# stripboard.net
KiCad netlist of a schematic drawn in EAGLE
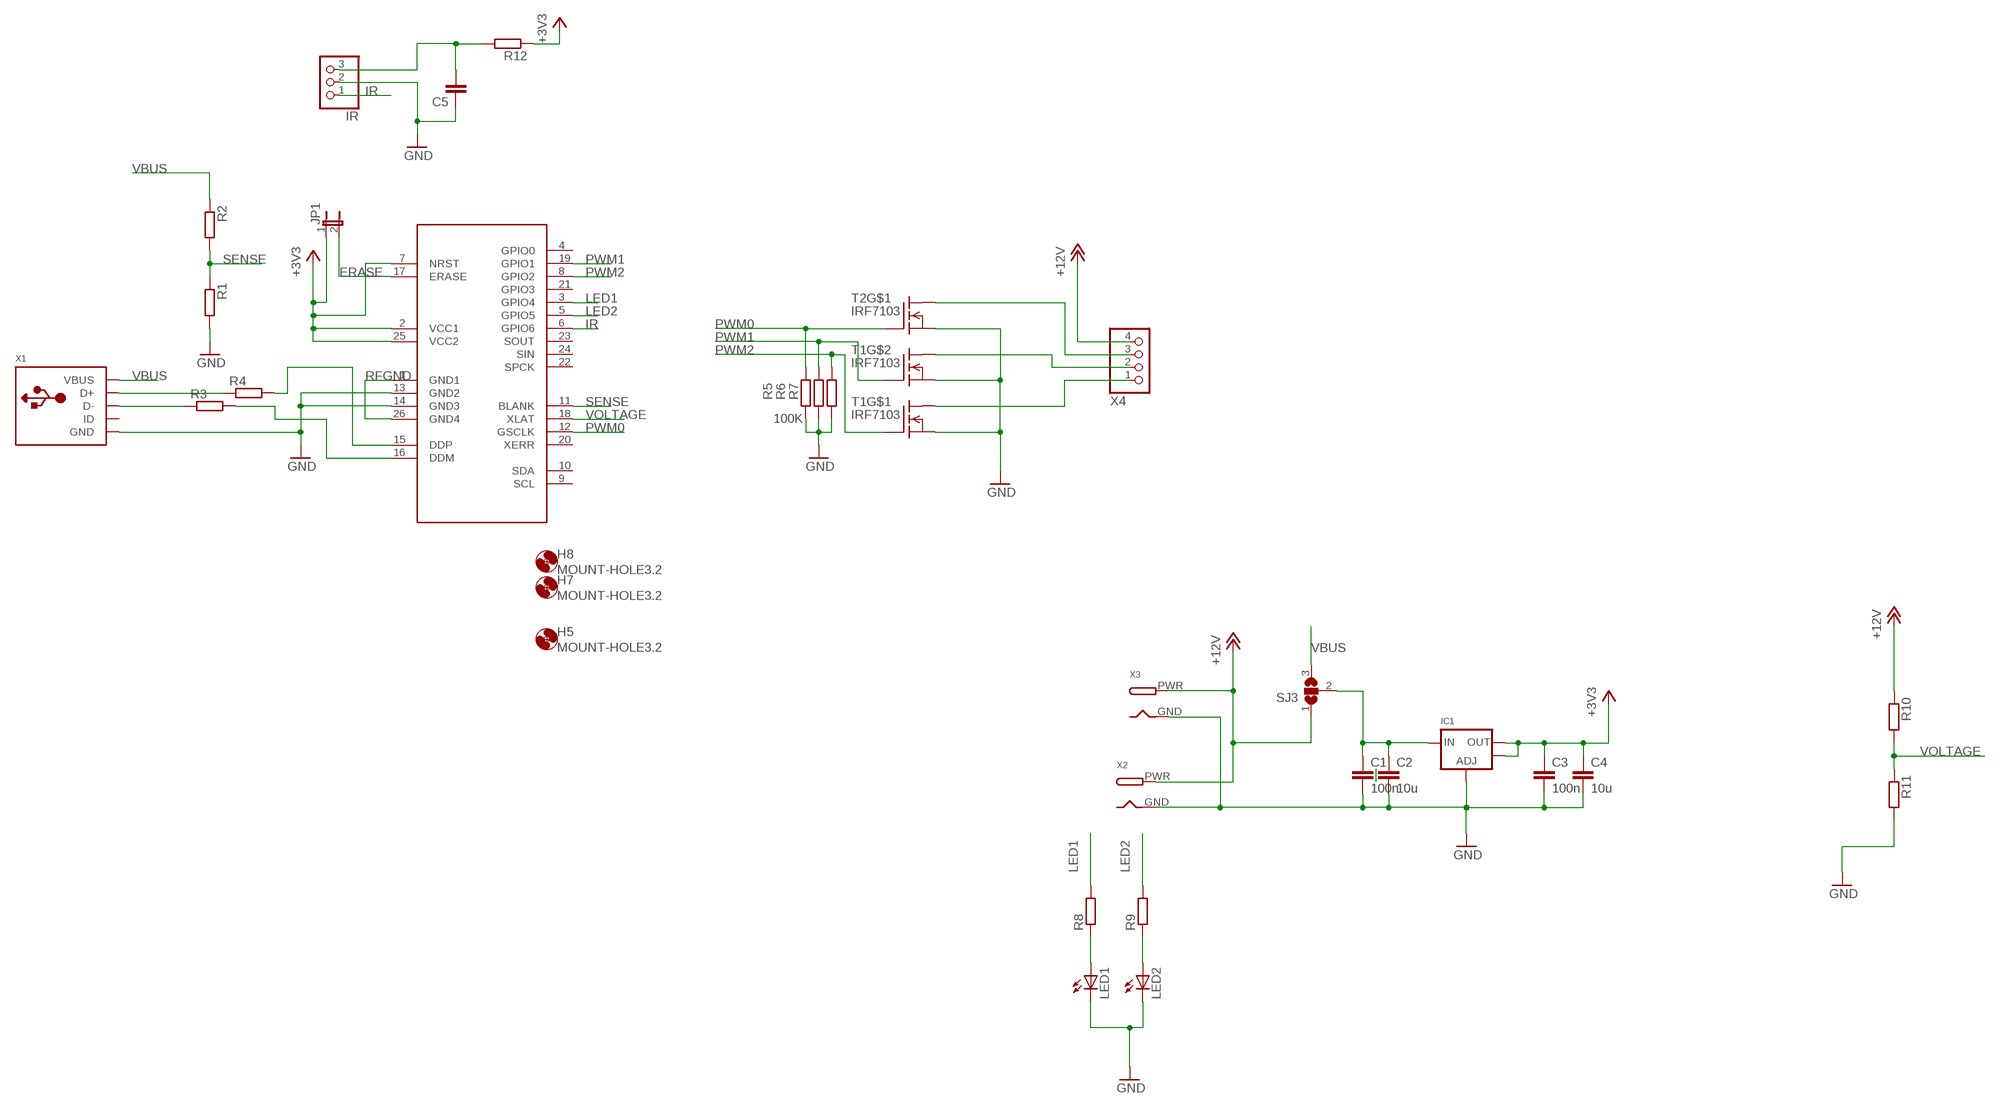
[diagram p0: schematic, sheet 1]

(export (version "E")
  (design (tool "Eeschema 10.0.6"))
  (components
    (comp (ref "C1")
      (value "100n")
      (footprint "eagle-import:C0805")
      (libsource (lib "eagle-import") (part "C-EUC0805"))
    )
    (comp (ref "C2")
      (value "10u")
      (footprint "eagle-import:C0805")
      (libsource (lib "eagle-import") (part "C-EUC0805"))
    )
    (comp (ref "C3")
      (value "100n")
      (footprint "eagle-import:C0805")
      (libsource (lib "eagle-import") (part "C-EUC0805"))
    )
    (comp (ref "C4")
      (value "10u")
      (footprint "eagle-import:C0805")
      (libsource (lib "eagle-import") (part "C-EUC0805"))
    )
    (comp (ref "C5")
      (value "C-EUC0805")
      (footprint "eagle-import:C0805")
      (libsource (lib "eagle-import") (part "C-EUC0805"))
    )
    (comp (ref "H5")
      (value "MOUNT-HOLE3.2")
      (footprint "eagle-import:3,2")
      (libsource (lib "eagle-import") (part "MOUNT-HOLE3.2"))
    )
    (comp (ref "H7")
      (value "MOUNT-HOLE3.2")
      (footprint "eagle-import:3,2")
      (libsource (lib "eagle-import") (part "MOUNT-HOLE3.2"))
    )
    (comp (ref "H8")
      (value "MOUNT-HOLE3.2")
      (footprint "eagle-import:3,2")
      (libsource (lib "eagle-import") (part "MOUNT-HOLE3.2"))
    )
    (comp (ref "IC1")
      (value "LM1117SOT223-REFLOW")
      (footprint "eagle-import:SOT223-R")
      (libsource (lib "eagle-import") (part "LM1117SOT223-REFLOW"))
    )
    (comp (ref "IR")
      (value "PINHD-1X3")
      (footprint "eagle-import:1X03")
      (libsource (lib "eagle-import") (part "PINHD-1X3"))
    )
    (comp (ref "JP1")
      (value "JP1E")
      (footprint "eagle-import:JP1")
      (libsource (lib "eagle-import") (part "JP1E"))
    )
    (comp (ref "LED1")
      (value "LEDCHIP-LED0805")
      (footprint "eagle-import:CHIP-LED0805")
      (libsource (lib "eagle-import") (part "LEDCHIP-LED0805"))
    )
    (comp (ref "LED2")
      (value "LEDCHIP-LED0805")
      (footprint "eagle-import:CHIP-LED0805")
      (libsource (lib "eagle-import") (part "LEDCHIP-LED0805"))
    )
    (comp (ref "R1")
      (value "R-EU_R0805")
      (footprint "eagle-import:R0805")
      (libsource (lib "eagle-import") (part "R-EU_R0805"))
    )
    (comp (ref "R2")
      (value "R-EU_R0805")
      (footprint "eagle-import:R0805")
      (libsource (lib "eagle-import") (part "R-EU_R0805"))
    )
    (comp (ref "R3")
      (value "R-EU_R0805")
      (footprint "eagle-import:R0805")
      (libsource (lib "eagle-import") (part "R-EU_R0805"))
    )
    (comp (ref "R4")
      (value "R-EU_R0805")
      (footprint "eagle-import:R0805")
      (libsource (lib "eagle-import") (part "R-EU_R0805"))
    )
    (comp (ref "R5")
      (value "100K")
      (footprint "eagle-import:M0805")
      (libsource (lib "eagle-import") (part "R-EU_M0805"))
    )
    (comp (ref "R6")
      (value "100K")
      (footprint "eagle-import:M0805")
      (libsource (lib "eagle-import") (part "R-EU_M0805"))
    )
    (comp (ref "R7")
      (value "100K")
      (footprint "eagle-import:M0805")
      (libsource (lib "eagle-import") (part "R-EU_M0805"))
    )
    (comp (ref "R8")
      (value "R-EU_R0805")
      (footprint "eagle-import:R0805")
      (libsource (lib "eagle-import") (part "R-EU_R0805"))
    )
    (comp (ref "R9")
      (value "R-EU_R0805")
      (footprint "eagle-import:R0805")
      (libsource (lib "eagle-import") (part "R-EU_R0805"))
    )
    (comp (ref "R10")
      (value "R-EU_R0805")
      (footprint "eagle-import:R0805")
      (libsource (lib "eagle-import") (part "R-EU_R0805"))
    )
    (comp (ref "R11")
      (value "R-EU_R0805")
      (footprint "eagle-import:R0805")
      (libsource (lib "eagle-import") (part "R-EU_R0805"))
    )
    (comp (ref "R12")
      (value "R-EU_R0805")
      (footprint "eagle-import:R0805")
      (libsource (lib "eagle-import") (part "R-EU_R0805"))
    )
    (comp (ref "SJ3")
      (value "SJ2W")
      (footprint "eagle-import:SJ_2")
      (libsource (lib "eagle-import") (part "SJ2W"))
    )
    (comp (ref "T1")
      (value "IRF7103")
      (footprint "eagle-import:SO-8")
      (libsource (lib "eagle-import") (part "IRF7103"))
    )
    (comp (ref "T2")
      (value "IRF7103")
      (footprint "eagle-import:SO-8")
      (libsource (lib "eagle-import") (part "IRF7103"))
    )
    (comp (ref "U$1")
      (value "RFBOARD")
      (footprint "eagle-import:RFBOARD")
      (libsource (lib "eagle-import") (part "RFBOARD"))
    )
    (comp (ref "X1")
      (value "USBMINIB")
      (footprint "eagle-import:USB-MINIB")
      (libsource (lib "eagle-import") (part "USBMINIB"))
    )
    (comp (ref "X2")
      (value "DCBARRELPTH")
      (footprint "eagle-import:DCJACK_2MM_PTH")
      (libsource (lib "eagle-import") (part "DCBARRELPTH"))
    )
    (comp (ref "X3")
      (value "DCBARRELPTH")
      (footprint "eagle-import:DCJACK_2MM_PTH")
      (libsource (lib "eagle-import") (part "DCBARRELPTH"))
    )
    (comp (ref "X4")
      (value "PINHD-1X4/90")
      (footprint "eagle-import:1X04_90")
      (libsource (lib "eagle-import") (part "PINHD-1X4/90"))
    )
  )
  (nets
    (net (code "1") (name "+3V3") (class "Default")
      (node (ref "C3") (pin "1") (pinfunction "1_1") (pintype "passive"))
      (node (ref "C4") (pin "1") (pinfunction "1_1") (pintype "passive"))
      (node (ref "IC1") (pin "2") (pinfunction "OUT_2") (pintype "passive"))
      (node (ref "IC1") (pin "4") (pinfunction "OUT1_4") (pintype "passive"))
      (node (ref "JP1") (pin "1") (pinfunction "1_1") (pintype "passive"))
      (node (ref "R12") (pin "1") (pinfunction "1_1") (pintype "passive"))
      (node (ref "U$1") (pin "2") (pinfunction "VCC1_2") (pintype "bidirectional"))
      (node (ref "U$1") (pin "25") (pinfunction "VCC2_25") (pintype "bidirectional"))
      (node (ref "U$1") (pin "7") (pinfunction "NRST_7") (pintype "bidirectional"))
    )
    (net (code "2") (name "+12V") (class "Default")
      (node (ref "R10") (pin "1") (pinfunction "1_1") (pintype "passive"))
      (node (ref "SJ3") (pin "1") (pinfunction "1_1") (pintype "passive"))
      (node (ref "X2") (pin "PWR") (pinfunction "PWR_PWR") (pintype "power_in"))
      (node (ref "X3") (pin "PWR") (pinfunction "PWR_PWR") (pintype "power_in"))
      (node (ref "X4") (pin "4") (pinfunction "4_4") (pintype "passive"))
    )
    (net (code "3") (name "/ERASE") (class "Default")
      (node (ref "JP1") (pin "2") (pinfunction "2_2") (pintype "passive"))
      (node (ref "U$1") (pin "17") (pinfunction "ERASE_17") (pintype "bidirectional"))
    )
    (net (code "4") (name "/IR") (class "Default")
      (node (ref "IR") (pin "1") (pinfunction "1_1") (pintype "passive"))
      (node (ref "U$1") (pin "6") (pinfunction "GPIO6_6") (pintype "bidirectional"))
    )
    (net (code "5") (name "/LED1") (class "Default")
      (node (ref "R8") (pin "2") (pinfunction "2_2") (pintype "passive"))
      (node (ref "U$1") (pin "3") (pinfunction "GPIO4_3") (pintype "bidirectional"))
    )
    (net (code "6") (name "/LED2") (class "Default")
      (node (ref "R9") (pin "2") (pinfunction "2_2") (pintype "passive"))
      (node (ref "U$1") (pin "5") (pinfunction "GPIO5_5") (pintype "bidirectional"))
    )
    (net (code "7") (name "/PWM0") (class "Default")
      (node (ref "R5") (pin "1") (pinfunction "1_1") (pintype "passive"))
      (node (ref "T2") (pin "2") (pinfunction "G_2") (pintype "passive"))
      (node (ref "U$1") (pin "12") (pinfunction "GSCLK_12") (pintype "bidirectional"))
    )
    (net (code "8") (name "/PWM1") (class "Default")
      (node (ref "R6") (pin "1") (pinfunction "1_1") (pintype "passive"))
      (node (ref "T1") (pin "4") (pinfunction "G_4") (pintype "passive"))
      (node (ref "U$1") (pin "19") (pinfunction "GPIO1_19") (pintype "bidirectional"))
    )
    (net (code "9") (name "/PWM2") (class "Default")
      (node (ref "R7") (pin "1") (pinfunction "1_1") (pintype "passive"))
      (node (ref "T1") (pin "2") (pinfunction "G_2") (pintype "passive"))
      (node (ref "U$1") (pin "8") (pinfunction "GPIO2_8") (pintype "bidirectional"))
    )
    (net (code "10") (name "/RFGND") (class "Default")
      (node (ref "U$1") (pin "1") (pinfunction "GND1_1") (pintype "bidirectional"))
      (node (ref "U$1") (pin "26") (pinfunction "GND4_26") (pintype "bidirectional"))
    )
    (net (code "11") (name "/SENSE") (class "Default")
      (node (ref "R1") (pin "1") (pinfunction "1_1") (pintype "passive"))
      (node (ref "R2") (pin "2") (pinfunction "2_2") (pintype "passive"))
      (node (ref "U$1") (pin "11") (pinfunction "BLANK_11") (pintype "bidirectional"))
    )
    (net (code "12") (name "/VBUS") (class "Default")
      (node (ref "R2") (pin "1") (pinfunction "1_1") (pintype "passive"))
      (node (ref "SJ3") (pin "3") (pinfunction "3_3") (pintype "passive"))
      (node (ref "X1") (pin "VBUS") (pinfunction "VBUS_VBUS") (pintype "power_in"))
    )
    (net (code "13") (name "/VOLTAGE") (class "Default")
      (node (ref "R10") (pin "2") (pinfunction "2_2") (pintype "passive"))
      (node (ref "R11") (pin "1") (pinfunction "1_1") (pintype "passive"))
      (node (ref "U$1") (pin "18") (pinfunction "XLAT_18") (pintype "bidirectional"))
    )
    (net (code "14") (name "GND") (class "Default")
      (node (ref "C1") (pin "2") (pinfunction "2_2") (pintype "passive"))
      (node (ref "C2") (pin "2") (pinfunction "2_2") (pintype "passive"))
      (node (ref "C3") (pin "2") (pinfunction "2_2") (pintype "passive"))
      (node (ref "C4") (pin "2") (pinfunction "2_2") (pintype "passive"))
      (node (ref "C5") (pin "1") (pinfunction "1_1") (pintype "passive"))
      (node (ref "IC1") (pin "1") (pinfunction "ADJ_1") (pintype "input"))
      (node (ref "IR") (pin "2") (pinfunction "2_2") (pintype "passive"))
      (node (ref "LED1") (pin "C") (pinfunction "C_C") (pintype "passive"))
      (node (ref "LED2") (pin "C") (pinfunction "C_C") (pintype "passive"))
      (node (ref "R1") (pin "2") (pinfunction "2_2") (pintype "passive"))
      (node (ref "R11") (pin "2") (pinfunction "2_2") (pintype "passive"))
      (node (ref "R5") (pin "2") (pinfunction "2_2") (pintype "passive"))
      (node (ref "R6") (pin "2") (pinfunction "2_2") (pintype "passive"))
      (node (ref "R7") (pin "2") (pinfunction "2_2") (pintype "passive"))
      (node (ref "T1") (pin "1") (pinfunction "S_1") (pintype "passive"))
      (node (ref "T1") (pin "3") (pinfunction "S_3") (pintype "passive"))
      (node (ref "T2") (pin "1") (pinfunction "S_1") (pintype "passive"))
      (node (ref "U$1") (pin "13") (pinfunction "GND2_13") (pintype "bidirectional"))
      (node (ref "U$1") (pin "14") (pinfunction "GND3_14") (pintype "bidirectional"))
      (node (ref "X1") (pin "GND") (pinfunction "GND_GND") (pintype "power_in"))
      (node (ref "X2") (pin "GND") (pinfunction "GND_GND") (pintype "power_in"))
      (node (ref "X3") (pin "GND") (pinfunction "GND_GND") (pintype "power_in"))
    )
    (net (code "15") (name "Net-(C5-Pad2)") (class "Default")
      (node (ref "C5") (pin "2") (pinfunction "2_2") (pintype "passive"))
      (node (ref "IR") (pin "3") (pinfunction "3_3") (pintype "passive"))
      (node (ref "R12") (pin "2") (pinfunction "2_2") (pintype "passive"))
    )
    (net (code "16") (name "Net-(IC1-IN)") (class "Default")
      (node (ref "C1") (pin "1") (pinfunction "1_1") (pintype "passive"))
      (node (ref "C2") (pin "1") (pinfunction "1_1") (pintype "passive"))
      (node (ref "IC1") (pin "3") (pinfunction "IN_3") (pintype "input"))
      (node (ref "SJ3") (pin "2") (pinfunction "2_2") (pintype "passive"))
    )
    (net (code "17") (name "Net-(LED1-PadA)") (class "Default")
      (node (ref "LED1") (pin "A") (pinfunction "A_A") (pintype "passive"))
      (node (ref "R8") (pin "1") (pinfunction "1_1") (pintype "passive"))
    )
    (net (code "18") (name "Net-(LED2-PadA)") (class "Default")
      (node (ref "LED2") (pin "A") (pinfunction "A_A") (pintype "passive"))
      (node (ref "R9") (pin "1") (pinfunction "1_1") (pintype "passive"))
    )
    (net (code "19") (name "Net-(R3-Pad1)") (class "Default")
      (node (ref "R3") (pin "1") (pinfunction "1_1") (pintype "passive"))
      (node (ref "X1") (pin "D-") (pinfunction "D-_D-") (pintype "bidirectional"))
    )
    (net (code "20") (name "Net-(R4-Pad1)") (class "Default")
      (node (ref "R4") (pin "1") (pinfunction "1_1") (pintype "passive"))
      (node (ref "X1") (pin "D+") (pinfunction "D+_D+") (pintype "bidirectional"))
    )
    (net (code "21") (name "Net-(T1A-D1)") (class "Default")
      (node (ref "T1") (pin "8") (pinfunction "D1_8") (pintype "passive"))
      (node (ref "X4") (pin "1") (pinfunction "1_1") (pintype "passive"))
    )
    (net (code "22") (name "Net-(T1B-D1)") (class "Default")
      (node (ref "T1") (pin "5") (pinfunction "D1_5") (pintype "passive"))
      (node (ref "X4") (pin "2") (pinfunction "2_2") (pintype "passive"))
    )
    (net (code "23") (name "Net-(T2A-D1)") (class "Default")
      (node (ref "T2") (pin "8") (pinfunction "D1_8") (pintype "passive"))
      (node (ref "X4") (pin "3") (pinfunction "3_3") (pintype "passive"))
    )
    (net (code "24") (name "Net-(U$1-DDM)") (class "Default")
      (node (ref "R3") (pin "2") (pinfunction "2_2") (pintype "passive"))
      (node (ref "U$1") (pin "16") (pinfunction "DDM_16") (pintype "bidirectional"))
    )
    (net (code "25") (name "Net-(U$1-DDP)") (class "Default")
      (node (ref "R4") (pin "2") (pinfunction "2_2") (pintype "passive"))
      (node (ref "U$1") (pin "15") (pinfunction "DDP_15") (pintype "bidirectional"))
    )
    (net (code "26") (name "unconnected-(T1A-D-Pad7)") (class "Default")
      (node (ref "T1") (pin "7") (pinfunction "D_7") (pintype "passive"))
    )
    (net (code "27") (name "unconnected-(T1B-D-Pad6)") (class "Default")
      (node (ref "T1") (pin "6") (pinfunction "D_6") (pintype "passive"))
    )
    (net (code "28") (name "unconnected-(T2A-D-Pad7)") (class "Default")
      (node (ref "T2") (pin "7") (pinfunction "D_7") (pintype "passive"))
    )
    (net (code "29") (name "unconnected-(U$1-GPIO0-Pad4)") (class "Default")
      (node (ref "U$1") (pin "4") (pinfunction "GPIO0_4") (pintype "bidirectional"))
    )
    (net (code "30") (name "unconnected-(U$1-GPIO3-Pad21)") (class "Default")
      (node (ref "U$1") (pin "21") (pinfunction "GPIO3_21") (pintype "bidirectional"))
    )
    (net (code "31") (name "unconnected-(U$1-SCL-Pad9)") (class "Default")
      (node (ref "U$1") (pin "9") (pinfunction "SCL_9") (pintype "bidirectional"))
    )
    (net (code "32") (name "unconnected-(U$1-SDA-Pad10)") (class "Default")
      (node (ref "U$1") (pin "10") (pinfunction "SDA_10") (pintype "bidirectional"))
    )
    (net (code "33") (name "unconnected-(U$1-SIN-Pad24)") (class "Default")
      (node (ref "U$1") (pin "24") (pinfunction "SIN_24") (pintype "bidirectional"))
    )
    (net (code "34") (name "unconnected-(U$1-SOUT-Pad23)") (class "Default")
      (node (ref "U$1") (pin "23") (pinfunction "SOUT_23") (pintype "bidirectional"))
    )
    (net (code "35") (name "unconnected-(U$1-SPCK-Pad22)") (class "Default")
      (node (ref "U$1") (pin "22") (pinfunction "SPCK_22") (pintype "bidirectional"))
    )
    (net (code "36") (name "unconnected-(U$1-XERR-Pad20)") (class "Default")
      (node (ref "U$1") (pin "20") (pinfunction "XERR_20") (pintype "bidirectional"))
    )
    (net (code "37") (name "unconnected-(X1-PadID)") (class "Default")
      (node (ref "X1") (pin "ID") (pinfunction "ID_ID") (pintype "bidirectional"))
    )
  )
)
